# Oscilloscope.net
KiCad netlist of a schematic drawn in Altium Designer
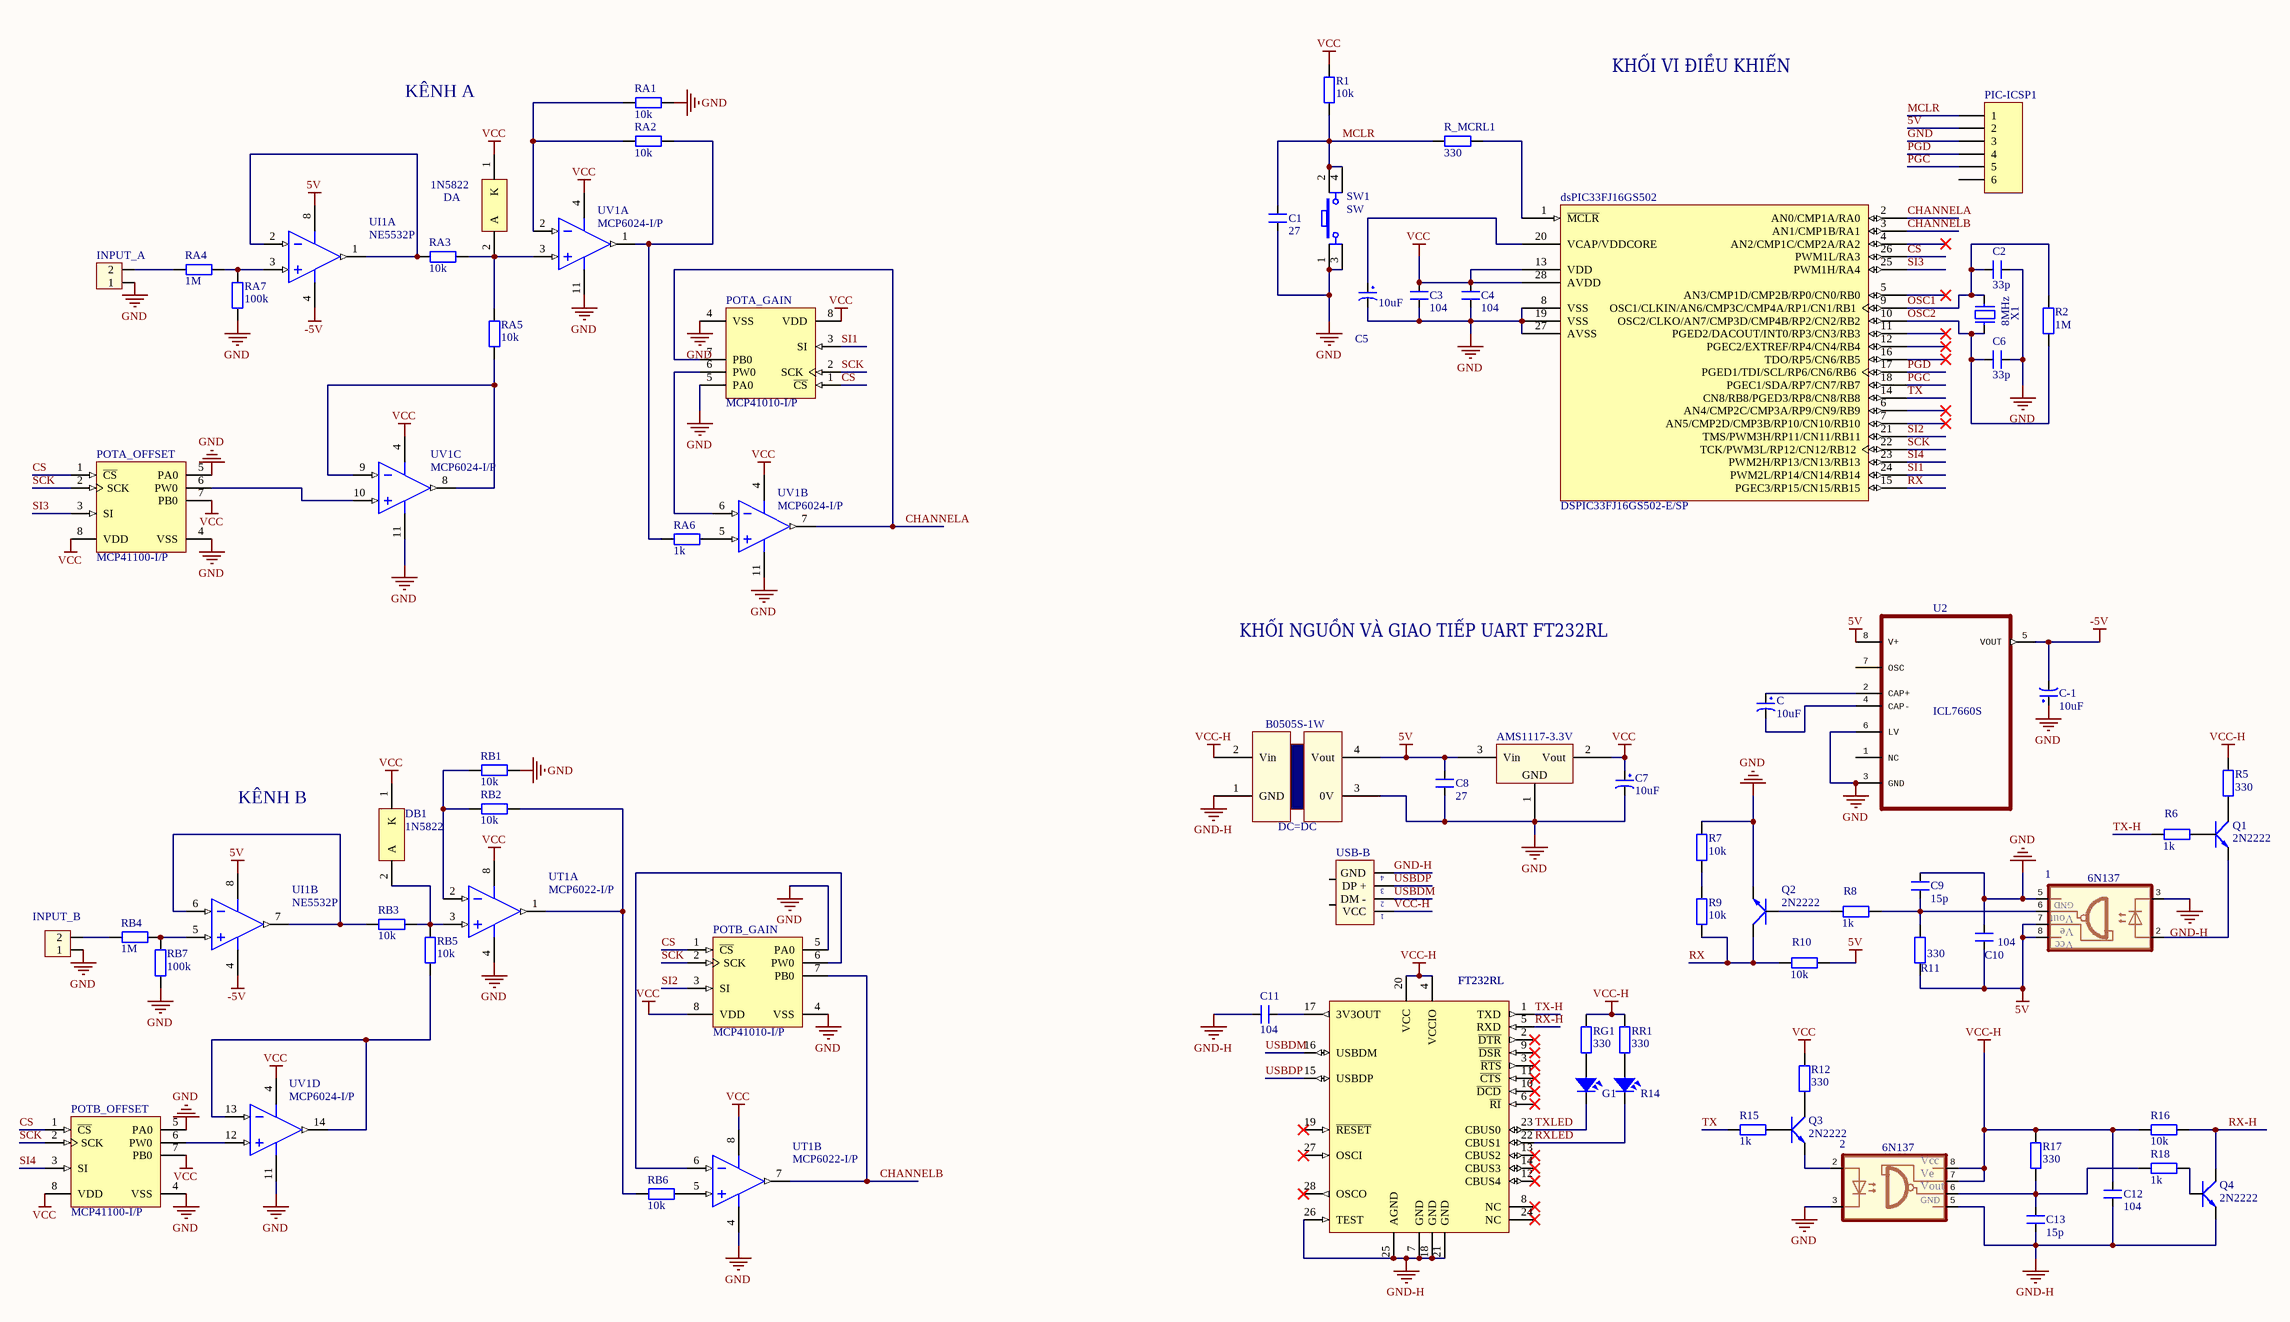
[diagram p0: Oscilloscope.SchDoc]

(export (version "E")
  (design (tool "Eeschema 10.0.6"))
  (components
    (comp (ref "1") (value "6N137") (footprint "DIP8/W0.3") (libsource (lib "6N137") (part "6N137")))
    (comp (ref "2") (value "6N137") (footprint "DIP8/W0.3") (libsource (lib "") (part "6N137_1")))
    (comp (ref "AMS1117-3.3V")
      (value "AMS1117-3V3")
      (footprint "TO-252")
      (libsource (lib "AMS1117-3V3") (part "AMS1117-3V3"))
    )
    (comp (ref "B0505S-1W")
      (value "DC=DC")
      (footprint "B050S-1W")
      (description "NGUON CACH LY")
      (libsource (lib "B0505S-1W") (part "B050S-1W"))
    )
    (comp (ref "C")
      (value "10uF")
      (footprint "CP1/2")
      (description "Cap P  0,1uF < 22uF , 16 - 50V")
      (libsource (lib "syhaunguyen") (part "CP1"))
    )
    (comp (ref "C-1")
      (value "10uF")
      (footprint "CP1/2")
      (description "Cap P  0,1uF < 22uF , 16 - 50V")
      (libsource (lib "syhaunguyen") (part "CP1"))
    )
    (comp (ref "C1")
      (value "27")
      (footprint "CN1.5")
      (description "Cap np 682pF => 104pF")
      (libsource (lib "syhaunguyen") (part "CN1.5"))
    )
    (comp (ref "C2")
      (value "33p")
      (footprint "CN1.5")
      (description "Cap np 682pF => 104pF")
      (libsource (lib "syhaunguyen") (part "CN1.5"))
    )
    (comp (ref "C3")
      (value "104")
      (footprint "CN1.5")
      (description "Cap np 682pF => 104pF")
      (libsource (lib "syhaunguyen") (part "CN1.5"))
    )
    (comp (ref "C4")
      (value "104")
      (footprint "CN1.5")
      (description "Cap np 682pF => 104pF")
      (libsource (lib "syhaunguyen") (part "CN1.5"))
    )
    (comp (ref "C5")
      (value "10uF")
      (footprint "CP1/2")
      (description "Cap P  0,1uF < 22uF , 16 - 50V")
      (libsource (lib "syhaunguyen") (part "CP1"))
    )
    (comp (ref "C6")
      (value "33p")
      (footprint "CN1.5")
      (description "Cap np 682pF => 104pF")
      (libsource (lib "syhaunguyen") (part "CN1.5"))
    )
    (comp (ref "C7")
      (value "10uF")
      (footprint "CP1/2")
      (description "Cap P  0,1uF < 22uF , 16 - 50V")
      (libsource (lib "syhaunguyen") (part "CP1"))
    )
    (comp (ref "C8")
      (value "27")
      (footprint "CN1.5")
      (description "Cap np 682pF => 104pF")
      (libsource (lib "syhaunguyen") (part "CN1.5"))
    )
    (comp (ref "C9")
      (value "15p")
      (footprint "CN1.5")
      (description "Cap np 682pF => 104pF")
      (libsource (lib "electronicvn-library1") (part "CN1.5"))
    )
    (comp (ref "C10")
      (value "104")
      (footprint "CN1.5")
      (description "Cap np 682pF => 104pF")
      (libsource (lib "electronicvn-library1") (part "CN1.5"))
    )
    (comp (ref "C11")
      (value "104")
      (footprint "CN1.5")
      (description "Cap np 682pF => 104pF")
      (libsource (lib "syhaunguyen") (part "CN1.5"))
    )
    (comp (ref "C12")
      (value "104")
      (footprint "CN1.5")
      (description "Cap np 682pF => 104pF")
      (libsource (lib "electronicvn-library1") (part "CN1.5"))
    )
    (comp (ref "C13")
      (value "15p")
      (footprint "CN1.5")
      (description "Cap np 682pF => 104pF")
      (libsource (lib "electronicvn-library1") (part "CN1.5"))
    )
    (comp (ref "DA")
      (value "1N5822")
      (footprint "ONSC-AXIAL_LEAD-2-267-05_V")
      (description "Rectifier, 2-Pin Axial_Lead, Bulk Bag")
      (fields (field (name "MANUFACTURER") "On Semiconductor"))
      (libsource (lib "ON Semi Schottky Diodes & Schottky Rectifiers") (part "1N5822"))
    )
    (comp (ref "DB1")
      (value "1N5822")
      (footprint "ONSC-AXIAL_LEAD-2-267-05_V")
      (description "Rectifier, 2-Pin Axial_Lead, Bulk Bag")
      (fields (field (name "MANUFACTURER") "On Semiconductor"))
      (libsource (lib "ON Semi Schottky Diodes & Schottky Rectifiers") (part "1N5822"))
    )
    (comp (ref "dsPIC33FJ16GS502")
      (value "DSPIC33FJ16GS502-E/SP")
      (footprint "Dallas Communication PCM Circuit:DIP28W")
      (fields (field (name "PUBLISHER") "Altium Limited"))
      (libsource (lib "Microchip DSC 16-Bit dsPIC33F") (part "DSPIC33FJ16GS502-E/SP"))
    )
    (comp (ref "FT232RL")
      (value "FT232RL")
      (footprint "DIP28W")
      (description "USB UART Asynchronous Serial Data Transfer Chip, 28-pin SSOP, Tube")
      (fields (field (name "MANUFACTURER") "FTDI") (field (name "PARTNUMBER") "FT232RL-Tube"))
      (libsource (lib "FTDI FT Series") (part "FT232RL-Tube"))
    )
    (comp (ref "G1")
      (value "LED")
      (footprint "LED-5-Green")
      (description "LED Single colour Green and Red")
      (libsource (lib "electronicvn-library1") (part "LED"))
    )
    (comp (ref "INPUT_A")
      (value "Header 2")
      (footprint "HED2")
      (description "Header 2 (Green)")
      (libsource (lib "syhaunguyen") (part "Hed2"))
    )
    (comp (ref "INPUT_B")
      (value "Header 2")
      (footprint "HED2")
      (description "Header 2 (Green)")
      (libsource (lib "syhaunguyen") (part "Hed2"))
    )
    (comp (ref "PIC-ICSP1")
      (value "PIC-ICSP-UART")
      (footprint "HDR1X6 - L")
      (description "Header, 6-Pin")
      (fields (field (name "PUBLISHER") "Altium Limited"))
      (libsource (lib "NBBLib 14-03-2012") (part "Header 6L"))
    )
    (comp (ref "POTA_GAIN")
      (value "MCP41010-I/P")
      (footprint "PDIP300-P8")
      (description "Single/Dual Digital Potentiometer with SPI Interface, 8-Pin PDIP, Industrial Temperature")
      (fields (field (name "PUBLISHER") "Altium Limited"))
      (libsource (lib "") (part "MCP41100-I/P_1"))
    )
    (comp (ref "POTA_OFFSET")
      (value "MCP41100-I/P")
      (footprint "PDIP300-P8")
      (description "Single/Dual Digital Potentiometer with SPI Interface, 8-Pin PDIP, Industrial Temperature")
      (fields (field (name "PUBLISHER") "Altium Limited"))
      (libsource (lib "Microchip Mixed Signal") (part "MCP41100-I/P"))
    )
    (comp (ref "POTB_GAIN")
      (value "MCP41010-I/P")
      (footprint "PDIP300-P8")
      (description "Single/Dual Digital Potentiometer with SPI Interface, 8-Pin PDIP, Industrial Temperature")
      (fields (field (name "PUBLISHER") "Altium Limited"))
      (libsource (lib "Microchip Mixed Signal") (part "MCP41100-I/P"))
    )
    (comp (ref "POTB_OFFSET")
      (value "MCP41100-I/P")
      (footprint "PDIP300-P8")
      (description "Single/Dual Digital Potentiometer with SPI Interface, 8-Pin PDIP, Industrial Temperature")
      (fields (field (name "PUBLISHER") "Altium Limited"))
      (libsource (lib "Microchip Mixed Signal") (part "MCP41100-I/P"))
    )
    (comp (ref "Q1")
      (value "2N2222")
      (footprint "QTO-92")
      (description "P 600mW, EBC")
      (libsource (lib "syhaunguyen") (part "NPN_EBC"))
    )
    (comp (ref "Q2")
      (value "2N2222")
      (footprint "QTO-92")
      (description "P 600mW, EBC")
      (libsource (lib "syhaunguyen") (part "NPN_EBC"))
    )
    (comp (ref "Q3")
      (value "2N2222")
      (footprint "QTO-92")
      (description "P 600mW, EBC")
      (libsource (lib "syhaunguyen") (part "NPN_EBC"))
    )
    (comp (ref "Q4")
      (value "2N2222")
      (footprint "QTO-92")
      (description "P 600mW, EBC")
      (libsource (lib "syhaunguyen") (part "NPN_EBC"))
    )
    (comp (ref "R1")
      (value "10k")
      (footprint "R1/2W")
      (description "Resistor 1/4W")
      (libsource (lib "syhaunguyen") (part "R1/4W"))
    )
    (comp (ref "R2")
      (value "1M")
      (footprint "R1/2W")
      (description "Resistor 1/4W")
      (libsource (lib "syhaunguyen") (part "R1/4W"))
    )
    (comp (ref "R5")
      (value "330")
      (footprint "R1/4W")
      (description "Resistor 1/4W")
      (libsource (lib "syhaunguyen") (part "R1/4W"))
    )
    (comp (ref "R6")
      (value "1k")
      (footprint "R1/4W")
      (description "Resistor 1/4W")
      (libsource (lib "syhaunguyen") (part "R1/4W"))
    )
    (comp (ref "R7")
      (value "10k")
      (footprint "R1/4W")
      (description "Resistor 1/4W")
      (libsource (lib "syhaunguyen") (part "R1/4W"))
    )
    (comp (ref "R8")
      (value "1k")
      (footprint "R1/4W")
      (description "Resistor 1/4W")
      (libsource (lib "syhaunguyen") (part "R1/4W"))
    )
    (comp (ref "R9")
      (value "10k")
      (footprint "R1/4W")
      (description "Resistor 1/4W")
      (libsource (lib "syhaunguyen") (part "R1/4W"))
    )
    (comp (ref "R10")
      (value "10k")
      (footprint "R1/4W")
      (description "Resistor 1/4W")
      (libsource (lib "syhaunguyen") (part "R1/4W"))
    )
    (comp (ref "R11")
      (value "330")
      (footprint "R1/4W")
      (description "Resistor 1/4W")
      (libsource (lib "syhaunguyen") (part "R1/4W"))
    )
    (comp (ref "R12")
      (value "330")
      (footprint "R1/4W")
      (description "Resistor 1/4W")
      (libsource (lib "syhaunguyen") (part "R1/4W"))
    )
    (comp (ref "R14")
      (value "LED")
      (footprint "LED-5-RED")
      (description "LED Single colour Green and Red")
      (libsource (lib "electronicvn-library1") (part "LED"))
    )
    (comp (ref "R15")
      (value "1k")
      (footprint "R1/4W")
      (description "Resistor 1/4W")
      (libsource (lib "syhaunguyen") (part "R1/4W"))
    )
    (comp (ref "R16")
      (value "10k")
      (footprint "R1/4W")
      (description "Resistor 1/4W")
      (libsource (lib "syhaunguyen") (part "R1/4W"))
    )
    (comp (ref "R17")
      (value "330")
      (footprint "R1/4W")
      (description "Resistor 1/4W")
      (libsource (lib "syhaunguyen") (part "R1/4W"))
    )
    (comp (ref "R18")
      (value "1k")
      (footprint "R1/4W")
      (description "Resistor 1/4W")
      (libsource (lib "syhaunguyen") (part "R1/4W"))
    )
    (comp (ref "RA1")
      (value "10k")
      (footprint "R1/2W")
      (description "Resistor 1/4W")
      (libsource (lib "syhaunguyen") (part "R1/4W"))
    )
    (comp (ref "RA2")
      (value "10k")
      (footprint "R1/2W")
      (description "Resistor 1/4W")
      (libsource (lib "syhaunguyen") (part "R1/4W"))
    )
    (comp (ref "RA3")
      (value "10k")
      (footprint "R1/2W")
      (description "Resistor 1/4W")
      (libsource (lib "syhaunguyen") (part "R1/4W"))
    )
    (comp (ref "RA4")
      (value "1M")
      (footprint "R1/2W")
      (description "Resistor 1/4W")
      (libsource (lib "syhaunguyen") (part "R1/4W"))
    )
    (comp (ref "RA5")
      (value "10k")
      (footprint "R1/2W")
      (description "Resistor 1/4W")
      (libsource (lib "syhaunguyen") (part "R1/4W"))
    )
    (comp (ref "RA6")
      (value "1k")
      (footprint "R1/2W")
      (description "Resistor 1/4W")
      (libsource (lib "syhaunguyen") (part "R1/4W"))
    )
    (comp (ref "RA7")
      (value "100k")
      (footprint "R1/2W")
      (description "Resistor 1/4W")
      (libsource (lib "syhaunguyen") (part "R1/4W"))
    )
    (comp (ref "RB1")
      (value "10k")
      (footprint "R1/2W")
      (description "Resistor 1/4W")
      (libsource (lib "syhaunguyen") (part "R1/4W"))
    )
    (comp (ref "RB2")
      (value "10k")
      (footprint "R1/2W")
      (description "Resistor 1/4W")
      (libsource (lib "syhaunguyen") (part "R1/4W"))
    )
    (comp (ref "RB3")
      (value "10k")
      (footprint "R1/2W")
      (description "Resistor 1/4W")
      (libsource (lib "syhaunguyen") (part "R1/4W"))
    )
    (comp (ref "RB4")
      (value "1M")
      (footprint "R1/2W")
      (description "Resistor 1/4W")
      (libsource (lib "syhaunguyen") (part "R1/4W"))
    )
    (comp (ref "RB5")
      (value "10k")
      (footprint "R1/2W")
      (description "Resistor 1/4W")
      (libsource (lib "syhaunguyen") (part "R1/4W"))
    )
    (comp (ref "RB6")
      (value "10k")
      (footprint "R1/2W")
      (description "Resistor 1/4W")
      (libsource (lib "syhaunguyen") (part "R1/4W"))
    )
    (comp (ref "RB7")
      (value "100k")
      (footprint "R1/2W")
      (description "Resistor 1/4W")
      (libsource (lib "syhaunguyen") (part "R1/4W"))
    )
    (comp (ref "RG1")
      (value "330")
      (footprint "R1/4W")
      (description "Resistor 1/4W")
      (libsource (lib "syhaunguyen") (part "R1/4W"))
    )
    (comp (ref "RR1")
      (value "330")
      (footprint "R1/4W")
      (description "Resistor 1/4W")
      (libsource (lib "syhaunguyen") (part "R1/4W"))
    )
    (comp (ref "R_MCRL1")
      (value "330")
      (footprint "R1/2W")
      (description "Resistor 1/4W")
      (libsource (lib "syhaunguyen") (part "R1/4W"))
    )
    (comp (ref "SW1")
      (value "SW")
      (footprint "SW4")
      (description "Switch button 4 pin")
      (libsource (lib "syhaunguyen") (part "SW4"))
    )
    (comp (ref "U2")
      (value "ICL7660S")
      (footprint "DIP-8")
      (libsource (lib "ICL7660CPAZ") (part "ICL7660CPAZ"))
    )
    (comp (ref "UI1")
      (value "NE5532P")
      (footprint "TI-P8")
      (fields (field (name "MANUFACTURER") "Texas Instruments"))
      (libsource (lib "TI Amplifiers and Linear Operational Amplifier General Purpose") (part "NE5532P"))
    )
    (comp (ref "USB-B")
      (value "USB")
      (footprint "USB-B-MALE")
      (description "USB connector")
      (libsource (lib "PART") (part "USB"))
    )
    (comp (ref "UT1")
      (value "MCP6022-I/P")
      (footprint "PDIP300-P8")
      (description "Rail-to-Rail Input/Output, 10 MHz Operational Amplifier, 8-Pin PDIP, Industrial Temperature")
      (fields (field (name "MANUFACTURER") "Microchip"))
      (libsource (lib "Microchip Linear") (part "MCP6022-I/P"))
    )
    (comp (ref "UV1")
      (value "MCP6024-I/P")
      (footprint "PDIP300-P14")
      (description "Rail-to-Rail Input/Output, 10 MHz Operational Amplifier, 14-Pin PDIP, Industrial Temperature")
      (fields (field (name "MANUFACTURER") "Microchip"))
      (libsource (lib "Microchip Linear") (part "MCP6024-I/P"))
    )
    (comp (ref "X1")
      (value "8MHz")
      (footprint "XT2")
      (description "Crystal For all Crystal 2pin.")
      (libsource (lib "PART") (part "XT2"))
    )
  )
  (nets
    (net (code "1") (name "-5V") (class "Default")
      (node (ref "C-1") (pin "2") (pinfunction "2_2") (pintype "passive"))
      (node (ref "U2") (pin "5") (pinfunction "VOUT_5") (pintype "output"))
      (node (ref "UI1") (pin "4") (pinfunction "VCC-_4") (pintype "power_in"))
    )
    (net (code "2") (name "/CHANNELA") (class "Default")
      (node (ref "POTA_GAIN") (pin "7") (pinfunction "PB0_7") (pintype "passive"))
      (node (ref "UV1") (pin "7") (pinfunction "VOUTB_7") (pintype "output"))
      (node (ref "dsPIC33FJ16GS502") (pin "2") (pinfunction "AN0/CMP1A/RA0_2") (pintype "bidirectional"))
    )
    (net (code "3") (name "/CHANNELB") (class "Default")
      (node (ref "POTB_GAIN") (pin "7") (pinfunction "PB0_7") (pintype "passive"))
      (node (ref "UT1") (pin "7") (pinfunction "VOUTB_7") (pintype "output"))
      (node (ref "dsPIC33FJ16GS502") (pin "3") (pinfunction "AN1/CMP1B/RA1_3") (pintype "bidirectional"))
    )
    (net (code "4") (name "/CS") (class "Default")
      (node (ref "POTA_GAIN") (pin "1") (pinfunction "~{CS}_1") (pintype "input"))
      (node (ref "POTA_OFFSET") (pin "1") (pinfunction "~{CS}_1") (pintype "input"))
      (node (ref "POTB_GAIN") (pin "1") (pinfunction "~{CS}_1") (pintype "input"))
      (node (ref "POTB_OFFSET") (pin "1") (pinfunction "~{CS}_1") (pintype "input"))
      (node (ref "dsPIC33FJ16GS502") (pin "26") (pinfunction "PWM1L/RA3_26") (pintype "bidirectional"))
    )
    (net (code "5") (name "/MCLR") (class "Default")
      (node (ref "C1") (pin "2") (pinfunction "2_2") (pintype "passive"))
      (node (ref "PIC-ICSP1") (pin "1") (pinfunction "1_1") (pintype "passive"))
      (node (ref "R1") (pin "1") (pinfunction "1_1") (pintype "passive"))
      (node (ref "R_MCRL1") (pin "2") (pinfunction "2_2") (pintype "passive"))
      (node (ref "SW1") (pin "2") (pintype "passive"))
      (node (ref "SW1") (pin "4") (pintype "passive"))
    )
    (net (code "6") (name "/OSC1") (class "Default")
      (node (ref "C2") (pin "1") (pinfunction "1_1") (pintype "passive"))
      (node (ref "R2") (pin "2") (pinfunction "2_2") (pintype "passive"))
      (node (ref "X1") (pin "2") (pinfunction "2_2") (pintype "passive"))
      (node (ref "dsPIC33FJ16GS502") (pin "9") (pinfunction "OSC1/CLKIN/AN6/CMP3C/CMP4A/RP1/CN1/RB1_9") (pintype "bidirectional"))
    )
    (net (code "7") (name "/OSC2") (class "Default")
      (node (ref "C6") (pin "1") (pinfunction "1_1") (pintype "passive"))
      (node (ref "R2") (pin "1") (pinfunction "1_1") (pintype "passive"))
      (node (ref "X1") (pin "1") (pinfunction "1_1") (pintype "passive"))
      (node (ref "dsPIC33FJ16GS502") (pin "10") (pinfunction "OSC2/CLKO/AN7/CMP3D/CMP4B/RP2/CN2/RB2_10") (pintype "bidirectional"))
    )
    (net (code "8") (name "/PGC") (class "Default")
      (node (ref "PIC-ICSP1") (pin "5") (pinfunction "5_5") (pintype "passive"))
      (node (ref "dsPIC33FJ16GS502") (pin "18") (pinfunction "PGEC1/SDA/RP7/CN7/RB7_18") (pintype "bidirectional"))
    )
    (net (code "9") (name "/PGD") (class "Default")
      (node (ref "PIC-ICSP1") (pin "4") (pinfunction "4_4") (pintype "passive"))
      (node (ref "dsPIC33FJ16GS502") (pin "17") (pinfunction "PGED1/TDI/SCL/RP6/CN6/RB6_17") (pintype "bidirectional"))
    )
    (net (code "10") (name "/RX") (class "Default")
      (node (ref "Q2") (pin "3") (pinfunction "C_3") (pintype "passive"))
      (node (ref "R10") (pin "1") (pinfunction "1_1") (pintype "passive"))
      (node (ref "R9") (pin "1") (pinfunction "1_1") (pintype "passive"))
      (node (ref "dsPIC33FJ16GS502") (pin "15") (pinfunction "PGEC3/RP15/CN15/RB15_15") (pintype "bidirectional"))
    )
    (net (code "11") (name "/RX-H") (class "Default")
      (node (ref "FT232RL") (pin "5") (pinfunction "RXD_5") (pintype "input"))
      (node (ref "Q4") (pin "3") (pinfunction "C_3") (pintype "passive"))
      (node (ref "R16") (pin "2") (pinfunction "2_2") (pintype "passive"))
    )
    (net (code "12") (name "/RXLED") (class "Default")
      (node (ref "FT232RL") (pin "22") (pinfunction "CBUS1_22") (pintype "bidirectional"))
      (node (ref "R14") (pin "2") (pinfunction "2_2") (pintype "passive"))
    )
    (net (code "13") (name "/SCK") (class "Default")
      (node (ref "POTA_GAIN") (pin "2") (pinfunction "SCK_2") (pintype "input"))
      (node (ref "POTA_OFFSET") (pin "2") (pinfunction "SCK_2") (pintype "input"))
      (node (ref "POTB_GAIN") (pin "2") (pinfunction "SCK_2") (pintype "input"))
      (node (ref "POTB_OFFSET") (pin "2") (pinfunction "SCK_2") (pintype "input"))
      (node (ref "dsPIC33FJ16GS502") (pin "22") (pinfunction "TCK/PWM3L/RP12/CN12/RB12_22") (pintype "bidirectional"))
    )
    (net (code "14") (name "/SI1") (class "Default")
      (node (ref "POTA_GAIN") (pin "3") (pinfunction "SI_3") (pintype "input"))
      (node (ref "dsPIC33FJ16GS502") (pin "24") (pinfunction "PWM2L/RP14/CN14/RB14_24") (pintype "bidirectional"))
    )
    (net (code "15") (name "/SI2") (class "Default")
      (node (ref "POTB_GAIN") (pin "3") (pinfunction "SI_3") (pintype "input"))
      (node (ref "dsPIC33FJ16GS502") (pin "21") (pinfunction "TMS/PWM3H/RP11/CN11/RB11_21") (pintype "bidirectional"))
    )
    (net (code "16") (name "/SI3") (class "Default")
      (node (ref "POTA_OFFSET") (pin "3") (pinfunction "SI_3") (pintype "input"))
      (node (ref "dsPIC33FJ16GS502") (pin "25") (pinfunction "PWM1H/RA4_25") (pintype "bidirectional"))
    )
    (net (code "17") (name "/SI4") (class "Default")
      (node (ref "POTB_OFFSET") (pin "3") (pinfunction "SI_3") (pintype "input"))
      (node (ref "dsPIC33FJ16GS502") (pin "23") (pinfunction "PWM2H/RP13/CN13/RB13_23") (pintype "bidirectional"))
    )
    (net (code "18") (name "/TX") (class "Default")
      (node (ref "R15") (pin "1") (pinfunction "1_1") (pintype "passive"))
      (node (ref "dsPIC33FJ16GS502") (pin "14") (pinfunction "CN8/RB8/PGED3/RP8/CN8/RB8_14") (pintype "bidirectional"))
    )
    (net (code "19") (name "/TX-H") (class "Default")
      (node (ref "FT232RL") (pin "1") (pinfunction "TXD_1") (pintype "output"))
      (node (ref "R6") (pin "1") (pinfunction "1_1") (pintype "passive"))
    )
    (net (code "20") (name "/TXLED") (class "Default")
      (node (ref "FT232RL") (pin "23") (pinfunction "CBUS0_23") (pintype "bidirectional"))
      (node (ref "G1") (pin "2") (pinfunction "2_2") (pintype "passive"))
    )
    (net (code "21") (name "/USBDM") (class "Default")
      (node (ref "FT232RL") (pin "16") (pinfunction "USBDM_16") (pintype "bidirectional"))
      (node (ref "USB-B") (pin "2") (pinfunction "DM_-_2") (pintype "passive"))
    )
    (net (code "22") (name "/USBDP") (class "Default")
      (node (ref "FT232RL") (pin "15") (pinfunction "USBDP_15") (pintype "bidirectional"))
      (node (ref "USB-B") (pin "3") (pinfunction "DP_+_3") (pintype "passive"))
    )
    (net (code "23") (name "5V") (class "Default")
      (node (ref "1") (pin "7") (pinfunction "VE_7") (pintype "passive"))
      (node (ref "1") (pin "8") (pinfunction "VCC_8") (pintype "passive"))
      (node (ref "AMS1117-3.3V") (pin "3") (pinfunction "Vin_3") (pintype "power_in"))
      (node (ref "B0505S-1W") (pin "4") (pinfunction "Vout_4") (pintype "passive"))
      (node (ref "C10") (pin "1") (pinfunction "1_1") (pintype "passive"))
      (node (ref "C8") (pin "2") (pinfunction "2_2") (pintype "passive"))
      (node (ref "PIC-ICSP1") (pin "2") (pinfunction "2_2") (pintype "passive"))
      (node (ref "R10") (pin "2") (pinfunction "2_2") (pintype "passive"))
      (node (ref "R11") (pin "1") (pinfunction "1_1") (pintype "passive"))
      (node (ref "U2") (pin "8") (pinfunction "V+_8") (pintype "power_in"))
      (node (ref "UI1") (pin "8") (pinfunction "VCC+_8") (pintype "power_in"))
    )
    (net (code "24") (name "GND") (class "Default")
      (node (ref "1") (pin "5") (pinfunction "GND_5") (pintype "passive"))
      (node (ref "2") (pin "3") (pinfunction "C_3") (pintype "passive"))
      (node (ref "AMS1117-3.3V") (pin "1") (pinfunction "GND_1") (pintype "power_in"))
      (node (ref "B0505S-1W") (pin "3") (pinfunction "0V_3") (pintype "passive"))
      (node (ref "C-1") (pin "1") (pinfunction "1_1") (pintype "passive"))
      (node (ref "C1") (pin "1") (pinfunction "1_1") (pintype "passive"))
      (node (ref "C10") (pin "2") (pinfunction "2_2") (pintype "passive"))
      (node (ref "C2") (pin "2") (pinfunction "2_2") (pintype "passive"))
      (node (ref "C3") (pin "1") (pinfunction "1_1") (pintype "passive"))
      (node (ref "C4") (pin "1") (pinfunction "1_1") (pintype "passive"))
      (node (ref "C5") (pin "2") (pinfunction "2_2") (pintype "passive"))
      (node (ref "C6") (pin "2") (pinfunction "2_2") (pintype "passive"))
      (node (ref "C7") (pin "2") (pinfunction "2_2") (pintype "passive"))
      (node (ref "C8") (pin "1") (pinfunction "1_1") (pintype "passive"))
      (node (ref "C9") (pin "2") (pinfunction "2_2") (pintype "passive"))
      (node (ref "INPUT_A") (pin "1") (pinfunction "1_1") (pintype "passive"))
      (node (ref "INPUT_B") (pin "1") (pinfunction "1_1") (pintype "passive"))
      (node (ref "PIC-ICSP1") (pin "3") (pinfunction "3_3") (pintype "passive"))
      (node (ref "POTA_GAIN") (pin "4") (pinfunction "VSS_4") (pintype "power_in"))
      (node (ref "POTA_GAIN") (pin "5") (pinfunction "PA0_5") (pintype "passive"))
      (node (ref "POTA_OFFSET") (pin "4") (pinfunction "VSS_4") (pintype "power_in"))
      (node (ref "POTA_OFFSET") (pin "5") (pinfunction "PA0_5") (pintype "passive"))
      (node (ref "POTB_GAIN") (pin "4") (pinfunction "VSS_4") (pintype "power_in"))
      (node (ref "POTB_GAIN") (pin "5") (pinfunction "PA0_5") (pintype "passive"))
      (node (ref "POTB_OFFSET") (pin "4") (pinfunction "VSS_4") (pintype "power_in"))
      (node (ref "POTB_OFFSET") (pin "5") (pinfunction "PA0_5") (pintype "passive"))
      (node (ref "Q2") (pin "1") (pinfunction "E_1") (pintype "passive"))
      (node (ref "R7") (pin "2") (pinfunction "2_2") (pintype "passive"))
      (node (ref "RA1") (pin "1") (pinfunction "1_1") (pintype "passive"))
      (node (ref "RA7") (pin "1") (pinfunction "1_1") (pintype "passive"))
      (node (ref "RB1") (pin "1") (pinfunction "1_1") (pintype "passive"))
      (node (ref "RB7") (pin "1") (pinfunction "1_1") (pintype "passive"))
      (node (ref "SW1") (pin "1") (pintype "passive"))
      (node (ref "SW1") (pin "3") (pintype "passive"))
      (node (ref "U2") (pin "3") (pinfunction "GND_3") (pintype "passive"))
      (node (ref "U2") (pin "6") (pinfunction "LV_6") (pintype "passive"))
      (node (ref "UT1") (pin "4") (pinfunction "VSS_4") (pintype "power_in"))
      (node (ref "UV1") (pin "11") (pinfunction "VSS_11") (pintype "power_in"))
      (node (ref "dsPIC33FJ16GS502") (pin "19") (pinfunction "VSS_19") (pintype "power_in"))
      (node (ref "dsPIC33FJ16GS502") (pin "27") (pinfunction "AVSS_27") (pintype "power_in"))
      (node (ref "dsPIC33FJ16GS502") (pin "8") (pinfunction "VSS_8") (pintype "power_in"))
    )
    (net (code "25") (name "GND-H") (class "Default")
      (node (ref "1") (pin "3") (pinfunction "C_3") (pintype "passive"))
      (node (ref "2") (pin "5") (pinfunction "GND_5") (pintype "passive"))
      (node (ref "B0505S-1W") (pin "1") (pinfunction "GND_1") (pintype "passive"))
      (node (ref "C11") (pin "1") (pinfunction "1_1") (pintype "passive"))
      (node (ref "C12") (pin "1") (pinfunction "1_1") (pintype "passive"))
      (node (ref "C13") (pin "1") (pinfunction "1_1") (pintype "passive"))
      (node (ref "FT232RL") (pin "18") (pinfunction "GND_18") (pintype "power_in"))
      (node (ref "FT232RL") (pin "21") (pinfunction "GND_21") (pintype "power_in"))
      (node (ref "FT232RL") (pin "25") (pinfunction "AGND_25") (pintype "power_in"))
      (node (ref "FT232RL") (pin "26") (pinfunction "TEST_26") (pintype "input"))
      (node (ref "FT232RL") (pin "7") (pinfunction "GND_7") (pintype "power_in"))
      (node (ref "Q4") (pin "1") (pinfunction "E_1") (pintype "passive"))
      (node (ref "USB-B") (pin "4") (pinfunction "GND_4") (pintype "passive"))
    )
    (net (code "26") (name "Net-(1-A)") (class "Default")
      (node (ref "1") (pin "2") (pinfunction "A_2") (pintype "passive"))
      (node (ref "Q1") (pin "1") (pinfunction "E_1") (pintype "passive"))
    )
    (net (code "27") (name "Net-(1-VO)") (class "Default")
      (node (ref "1") (pin "6") (pinfunction "VO_6") (pintype "passive"))
      (node (ref "C9") (pin "1") (pinfunction "1_1") (pintype "passive"))
      (node (ref "R11") (pin "2") (pinfunction "2_2") (pintype "passive"))
      (node (ref "R8") (pin "2") (pinfunction "2_2") (pintype "passive"))
    )
    (net (code "28") (name "Net-(2-A)") (class "Default")
      (node (ref "2") (pin "2") (pinfunction "A_2") (pintype "passive"))
      (node (ref "Q3") (pin "1") (pinfunction "E_1") (pintype "passive"))
    )
    (net (code "29") (name "Net-(2-VO)") (class "Default")
      (node (ref "2") (pin "6") (pinfunction "VO_6") (pintype "passive"))
      (node (ref "C13") (pin "2") (pinfunction "2_2") (pintype "passive"))
      (node (ref "R17") (pin "1") (pinfunction "1_1") (pintype "passive"))
      (node (ref "R18") (pin "1") (pinfunction "1_1") (pintype "passive"))
    )
    (net (code "30") (name "Net-(DA-A)") (class "Default")
      (node (ref "DA") (pin "2") (pinfunction "A_2") (pintype "passive"))
      (node (ref "RA3") (pin "1") (pinfunction "1_1") (pintype "passive"))
      (node (ref "RA5") (pin "1") (pinfunction "1_1") (pintype "passive"))
      (node (ref "UV1") (pin "3") (pinfunction "VINA+_3") (pintype "input"))
    )
    (net (code "31") (name "Net-(DB1-A)") (class "Default")
      (node (ref "DB1") (pin "2") (pinfunction "A_2") (pintype "passive"))
      (node (ref "RB3") (pin "1") (pinfunction "1_1") (pintype "passive"))
      (node (ref "RB5") (pin "2") (pinfunction "2_2") (pintype "passive"))
      (node (ref "UT1") (pin "3") (pinfunction "VINA+_3") (pintype "input"))
    )
    (net (code "32") (name "Net-(FT232RL-3V3OUT)") (class "Default")
      (node (ref "C11") (pin "2") (pinfunction "2_2") (pintype "passive"))
      (node (ref "FT232RL") (pin "17") (pinfunction "3V3OUT_17") (pintype "output"))
    )
    (net (code "33") (name "Net-(G1-Pad1)") (class "Default")
      (node (ref "G1") (pin "1") (pinfunction "1_1") (pintype "passive"))
      (node (ref "RG1") (pin "1") (pinfunction "1_1") (pintype "passive"))
    )
    (net (code "34") (name "Net-(INPUT_A-Pad2)") (class "Default")
      (node (ref "INPUT_A") (pin "2") (pinfunction "2_2") (pintype "passive"))
      (node (ref "RA4") (pin "2") (pinfunction "2_2") (pintype "passive"))
    )
    (net (code "35") (name "Net-(INPUT_B-Pad2)") (class "Default")
      (node (ref "INPUT_B") (pin "2") (pinfunction "2_2") (pintype "passive"))
      (node (ref "RB4") (pin "2") (pinfunction "2_2") (pintype "passive"))
    )
    (net (code "36") (name "Net-(POTA_GAIN-PW0)") (class "Default")
      (node (ref "POTA_GAIN") (pin "6") (pinfunction "PW0_6") (pintype "passive"))
      (node (ref "UV1") (pin "6") (pinfunction "VINB-_6") (pintype "input"))
    )
    (net (code "37") (name "Net-(POTA_OFFSET-PW0)") (class "Default")
      (node (ref "POTA_OFFSET") (pin "6") (pinfunction "PW0_6") (pintype "passive"))
      (node (ref "UV1") (pin "10") (pinfunction "VINC+_10") (pintype "input"))
    )
    (net (code "38") (name "Net-(POTB_GAIN-PW0)") (class "Default")
      (node (ref "POTB_GAIN") (pin "6") (pinfunction "PW0_6") (pintype "passive"))
      (node (ref "UT1") (pin "6") (pinfunction "VINB-_6") (pintype "input"))
    )
    (net (code "39") (name "Net-(POTB_OFFSET-PW0)") (class "Default")
      (node (ref "POTB_OFFSET") (pin "6") (pinfunction "PW0_6") (pintype "passive"))
      (node (ref "UV1") (pin "12") (pinfunction "VIND+_12") (pintype "input"))
    )
    (net (code "40") (name "Net-(Q1-B)") (class "Default")
      (node (ref "Q1") (pin "2") (pinfunction "B_2") (pintype "passive"))
      (node (ref "R6") (pin "2") (pinfunction "2_2") (pintype "passive"))
    )
    (net (code "41") (name "Net-(Q1-C)") (class "Default")
      (node (ref "Q1") (pin "3") (pinfunction "C_3") (pintype "passive"))
      (node (ref "R5") (pin "1") (pinfunction "1_1") (pintype "passive"))
    )
    (net (code "42") (name "Net-(Q2-B)") (class "Default")
      (node (ref "Q2") (pin "2") (pinfunction "B_2") (pintype "passive"))
      (node (ref "R8") (pin "1") (pinfunction "1_1") (pintype "passive"))
    )
    (net (code "43") (name "Net-(Q3-B)") (class "Default")
      (node (ref "Q3") (pin "2") (pinfunction "B_2") (pintype "passive"))
      (node (ref "R15") (pin "2") (pinfunction "2_2") (pintype "passive"))
    )
    (net (code "44") (name "Net-(Q3-C)") (class "Default")
      (node (ref "Q3") (pin "3") (pinfunction "C_3") (pintype "passive"))
      (node (ref "R12") (pin "1") (pinfunction "1_1") (pintype "passive"))
    )
    (net (code "45") (name "Net-(Q4-B)") (class "Default")
      (node (ref "Q4") (pin "2") (pinfunction "B_2") (pintype "passive"))
      (node (ref "R18") (pin "2") (pinfunction "2_2") (pintype "passive"))
    )
    (net (code "46") (name "Net-(R7-Pad1)") (class "Default")
      (node (ref "R7") (pin "1") (pinfunction "1_1") (pintype "passive"))
      (node (ref "R9") (pin "2") (pinfunction "2_2") (pintype "passive"))
    )
    (net (code "47") (name "Net-(R14-Pad1)") (class "Default")
      (node (ref "R14") (pin "1") (pinfunction "1_1") (pintype "passive"))
      (node (ref "RR1") (pin "1") (pinfunction "1_1") (pintype "passive"))
    )
    (net (code "48") (name "Net-(U2-CAP+)") (class "Default")
      (node (ref "C") (pin "1") (pinfunction "1_1") (pintype "passive"))
      (node (ref "U2") (pin "2") (pinfunction "CAP+_2") (pintype "passive"))
    )
    (net (code "49") (name "Net-(U2-CAP-)") (class "Default")
      (node (ref "C") (pin "2") (pinfunction "2_2") (pintype "passive"))
      (node (ref "U2") (pin "4") (pinfunction "CAP-_4") (pintype "passive"))
    )
    (net (code "50") (name "Net-(UI1A-IN1+)") (class "Default")
      (node (ref "RA4") (pin "1") (pinfunction "1_1") (pintype "passive"))
      (node (ref "RA7") (pin "2") (pinfunction "2_2") (pintype "passive"))
      (node (ref "UI1") (pin "3") (pinfunction "IN1+_3") (pintype "input"))
    )
    (net (code "51") (name "Net-(UI1A-IN1-)") (class "Default")
      (node (ref "RA3") (pin "2") (pinfunction "2_2") (pintype "passive"))
      (node (ref "UI1") (pin "1") (pinfunction "OUT1_1") (pintype "output"))
      (node (ref "UI1") (pin "2") (pinfunction "IN1-_2") (pintype "input"))
    )
    (net (code "52") (name "Net-(UI1B-IN2+)") (class "Default")
      (node (ref "RB4") (pin "1") (pinfunction "1_1") (pintype "passive"))
      (node (ref "RB7") (pin "2") (pinfunction "2_2") (pintype "passive"))
      (node (ref "UI1") (pin "5") (pinfunction "IN2+_5") (pintype "input"))
    )
    (net (code "53") (name "Net-(UI1B-IN2-)") (class "Default")
      (node (ref "RB3") (pin "2") (pinfunction "2_2") (pintype "passive"))
      (node (ref "UI1") (pin "6") (pinfunction "IN2-_6") (pintype "input"))
      (node (ref "UI1") (pin "7") (pinfunction "OUT2_7") (pintype "output"))
    )
    (net (code "54") (name "Net-(UT1A-VINA-)") (class "Default")
      (node (ref "RB1") (pin "2") (pinfunction "2_2") (pintype "passive"))
      (node (ref "RB2") (pin "2") (pinfunction "2_2") (pintype "passive"))
      (node (ref "UT1") (pin "2") (pinfunction "VINA-_2") (pintype "input"))
    )
    (net (code "55") (name "Net-(UT1A-VOUTA)") (class "Default")
      (node (ref "RB2") (pin "1") (pinfunction "1_1") (pintype "passive"))
      (node (ref "RB6") (pin "2") (pinfunction "2_2") (pintype "passive"))
      (node (ref "UT1") (pin "1") (pinfunction "VOUTA_1") (pintype "output"))
    )
    (net (code "56") (name "Net-(UT1B-VINB+)") (class "Default")
      (node (ref "RB6") (pin "1") (pinfunction "1_1") (pintype "passive"))
      (node (ref "UT1") (pin "5") (pinfunction "VINB+_5") (pintype "input"))
    )
    (net (code "57") (name "Net-(UV1A-VINA-)") (class "Default")
      (node (ref "RA1") (pin "2") (pinfunction "2_2") (pintype "passive"))
      (node (ref "RA2") (pin "2") (pinfunction "2_2") (pintype "passive"))
      (node (ref "UV1") (pin "2") (pinfunction "VINA-_2") (pintype "input"))
    )
    (net (code "58") (name "Net-(UV1A-VOUTA)") (class "Default")
      (node (ref "RA2") (pin "1") (pinfunction "1_1") (pintype "passive"))
      (node (ref "RA6") (pin "2") (pinfunction "2_2") (pintype "passive"))
      (node (ref "UV1") (pin "1") (pinfunction "VOUTA_1") (pintype "output"))
    )
    (net (code "59") (name "Net-(UV1B-VINB+)") (class "Default")
      (node (ref "RA6") (pin "1") (pinfunction "1_1") (pintype "passive"))
      (node (ref "UV1") (pin "5") (pinfunction "VINB+_5") (pintype "input"))
    )
    (net (code "60") (name "Net-(UV1C-VINC-)") (class "Default")
      (node (ref "RA5") (pin "2") (pinfunction "2_2") (pintype "passive"))
      (node (ref "UV1") (pin "8") (pinfunction "VOUTC_8") (pintype "output"))
      (node (ref "UV1") (pin "9") (pinfunction "VINC-_9") (pintype "input"))
    )
    (net (code "61") (name "Net-(UV1D-VIND-)") (class "Default")
      (node (ref "RB5") (pin "1") (pinfunction "1_1") (pintype "passive"))
      (node (ref "UV1") (pin "13") (pinfunction "VIND-_13") (pintype "input"))
      (node (ref "UV1") (pin "14") (pinfunction "VOUTD_14") (pintype "output"))
    )
    (net (code "62") (name "Net-(dsPIC33FJ16GS502-VCAP{slash}VDDCORE)") (class "Default")
      (node (ref "C5") (pin "1") (pinfunction "1_1") (pintype "passive"))
      (node (ref "dsPIC33FJ16GS502") (pin "20") (pinfunction "VCAP/VDDCORE_20") (pintype "power_in"))
    )
    (net (code "63") (name "Net-(dsPIC33FJ16GS502-~{MCLR})") (class "Default")
      (node (ref "R_MCRL1") (pin "1") (pinfunction "1_1") (pintype "passive"))
      (node (ref "dsPIC33FJ16GS502") (pin "1") (pinfunction "~{MCLR}_1") (pintype "input"))
    )
    (net (code "64") (name "VCC") (class "Default")
      (node (ref "AMS1117-3.3V") (pin "2") (pinfunction "Vout_2") (pintype "power_in"))
      (node (ref "C3") (pin "2") (pinfunction "2_2") (pintype "passive"))
      (node (ref "C4") (pin "2") (pinfunction "2_2") (pintype "passive"))
      (node (ref "C7") (pin "1") (pinfunction "1_1") (pintype "passive"))
      (node (ref "DA") (pin "1") (pinfunction "K_1") (pintype "passive"))
      (node (ref "DB1") (pin "1") (pinfunction "K_1") (pintype "passive"))
      (node (ref "POTA_GAIN") (pin "8") (pinfunction "VDD_8") (pintype "power_in"))
      (node (ref "POTA_OFFSET") (pin "7") (pinfunction "PB0_7") (pintype "passive"))
      (node (ref "POTA_OFFSET") (pin "8") (pinfunction "VDD_8") (pintype "power_in"))
      (node (ref "POTB_GAIN") (pin "8") (pinfunction "VDD_8") (pintype "power_in"))
      (node (ref "POTB_OFFSET") (pin "7") (pinfunction "PB0_7") (pintype "passive"))
      (node (ref "POTB_OFFSET") (pin "8") (pinfunction "VDD_8") (pintype "power_in"))
      (node (ref "R1") (pin "2") (pinfunction "2_2") (pintype "passive"))
      (node (ref "R12") (pin "2") (pinfunction "2_2") (pintype "passive"))
      (node (ref "UT1") (pin "8") (pinfunction "VDD_8") (pintype "power_in"))
      (node (ref "UV1") (pin "4") (pinfunction "VDD_4") (pintype "power_in"))
      (node (ref "dsPIC33FJ16GS502") (pin "13") (pinfunction "VDD_13") (pintype "power_in"))
      (node (ref "dsPIC33FJ16GS502") (pin "28") (pinfunction "AVDD_28") (pintype "power_in"))
    )
    (net (code "65") (name "VCC-H") (class "Default")
      (node (ref "2") (pin "7") (pinfunction "VE_7") (pintype "passive"))
      (node (ref "2") (pin "8") (pinfunction "VCC_8") (pintype "passive"))
      (node (ref "B0505S-1W") (pin "2") (pinfunction "Vin_2") (pintype "passive"))
      (node (ref "C12") (pin "2") (pinfunction "2_2") (pintype "passive"))
      (node (ref "FT232RL") (pin "20") (pinfunction "VCC_20") (pintype "power_in"))
      (node (ref "FT232RL") (pin "4") (pinfunction "VCCIO_4") (pintype "power_in"))
      (node (ref "R16") (pin "1") (pinfunction "1_1") (pintype "passive"))
      (node (ref "R17") (pin "2") (pinfunction "2_2") (pintype "passive"))
      (node (ref "R5") (pin "2") (pinfunction "2_2") (pintype "passive"))
      (node (ref "RG1") (pin "2") (pinfunction "2_2") (pintype "passive"))
      (node (ref "RR1") (pin "2") (pinfunction "2_2") (pintype "passive"))
      (node (ref "USB-B") (pin "1") (pinfunction "VCC_1") (pintype "passive"))
    )
    (net (code "66") (name "unconnected-(FT232RL-CBUS2-Pad13)") (class "Default")
      (node (ref "FT232RL") (pin "13") (pinfunction "CBUS2_13") (pintype "bidirectional+no_connect"))
    )
    (net (code "67") (name "unconnected-(FT232RL-CBUS3-Pad14)") (class "Default")
      (node (ref "FT232RL") (pin "14") (pinfunction "CBUS3_14") (pintype "bidirectional+no_connect"))
    )
    (net (code "68") (name "unconnected-(FT232RL-CBUS4-Pad12)") (class "Default")
      (node (ref "FT232RL") (pin "12") (pinfunction "CBUS4_12") (pintype "bidirectional+no_connect"))
    )
    (net (code "69") (name "unconnected-(FT232RL-NC-Pad8)") (class "Default")
      (node (ref "FT232RL") (pin "8") (pinfunction "NC_8") (pintype "passive+no_connect"))
    )
    (net (code "70") (name "unconnected-(FT232RL-NC-Pad24)") (class "Default")
      (node (ref "FT232RL") (pin "24") (pinfunction "NC_24") (pintype "passive+no_connect"))
    )
    (net (code "71") (name "unconnected-(FT232RL-OSCI-Pad27)") (class "Default")
      (node (ref "FT232RL") (pin "27") (pinfunction "OSCI_27") (pintype "input+no_connect"))
    )
    (net (code "72") (name "unconnected-(FT232RL-OSCO-Pad28)") (class "Default")
      (node (ref "FT232RL") (pin "28") (pinfunction "OSCO_28") (pintype "output+no_connect"))
    )
    (net (code "73") (name "unconnected-(FT232RL-~{CTS}-Pad11)") (class "Default")
      (node (ref "FT232RL") (pin "11") (pinfunction "~{CTS}_11") (pintype "input+no_connect"))
    )
    (net (code "74") (name "unconnected-(FT232RL-~{DCD}-Pad10)") (class "Default")
      (node (ref "FT232RL") (pin "10") (pinfunction "~{DCD}_10") (pintype "input+no_connect"))
    )
    (net (code "75") (name "unconnected-(FT232RL-~{DSR}-Pad9)") (class "Default")
      (node (ref "FT232RL") (pin "9") (pinfunction "~{DSR}_9") (pintype "input+no_connect"))
    )
    (net (code "76") (name "unconnected-(FT232RL-~{DTR}-Pad2)") (class "Default")
      (node (ref "FT232RL") (pin "2") (pinfunction "~{DTR}_2") (pintype "output+no_connect"))
    )
    (net (code "77") (name "unconnected-(FT232RL-~{RESET}-Pad19)") (class "Default")
      (node (ref "FT232RL") (pin "19") (pinfunction "~{RESET}_19") (pintype "input+no_connect"))
    )
    (net (code "78") (name "unconnected-(FT232RL-~{RI}-Pad6)") (class "Default")
      (node (ref "FT232RL") (pin "6") (pinfunction "~{RI}_6") (pintype "input+no_connect"))
    )
    (net (code "79") (name "unconnected-(FT232RL-~{RTS}-Pad3)") (class "Default")
      (node (ref "FT232RL") (pin "3") (pinfunction "~{RTS}_3") (pintype "output+no_connect"))
    )
    (net (code "80") (name "unconnected-(PIC-ICSP1-Pad6)") (class "Default")
      (node (ref "PIC-ICSP1") (pin "6") (pinfunction "6_6") (pintype "passive"))
    )
    (net (code "81") (name "unconnected-(U2-NC-Pad1)") (class "Default")
      (node (ref "U2") (pin "1") (pinfunction "NC_1") (pintype "passive"))
    )
    (net (code "82") (name "unconnected-(U2-OSC-Pad7)") (class "Default")
      (node (ref "U2") (pin "7") (pinfunction "OSC_7") (pintype "passive"))
    )
    (net (code "83") (name "unconnected-(USB-B-Pad5)") (class "Default")
      (node (ref "USB-B") (pin "5") (pinfunction "5_5") (pintype "passive"))
    )
    (net (code "84") (name "unconnected-(USB-B-Pad6)") (class "Default")
      (node (ref "USB-B") (pin "6") (pinfunction "6_6") (pintype "passive"))
    )
    (net (code "85") (name "unconnected-(dsPIC33FJ16GS502-AN2{slash}CMP1C{slash}CMP2A{slash}RA2-Pad4)") (class "Default")
      (node (ref "dsPIC33FJ16GS502") (pin "4") (pinfunction "AN2/CMP1C/CMP2A/RA2_4") (pintype "bidirectional+no_connect"))
    )
    (net (code "86") (name "unconnected-(dsPIC33FJ16GS502-AN3{slash}CMP1D{slash}CMP2B{slash}RP0{slash}CN0{slash}RB0-Pad5)") (class "Default")
      (node (ref "dsPIC33FJ16GS502") (pin "5") (pinfunction "AN3/CMP1D/CMP2B/RP0/CN0/RB0_5") (pintype "bidirectional+no_connect"))
    )
    (net (code "87") (name "unconnected-(dsPIC33FJ16GS502-AN4{slash}CMP2C{slash}CMP3A{slash}RP9{slash}CN9{slash}RB9-Pad6)") (class "Default")
      (node (ref "dsPIC33FJ16GS502") (pin "6") (pinfunction "AN4/CMP2C/CMP3A/RP9/CN9/RB9_6") (pintype "bidirectional+no_connect"))
    )
    (net (code "88") (name "unconnected-(dsPIC33FJ16GS502-AN5{slash}CMP2D{slash}CMP3B{slash}RP10{slash}CN10{slash}RB10-Pad7)") (class "Default")
      (node (ref "dsPIC33FJ16GS502") (pin "7") (pinfunction "AN5/CMP2D/CMP3B/RP10/CN10/RB10_7") (pintype "bidirectional+no_connect"))
    )
    (net (code "89") (name "unconnected-(dsPIC33FJ16GS502-PGEC2{slash}EXTREF{slash}RP4{slash}CN4{slash}RB4-Pad12)") (class "Default")
      (node (ref "dsPIC33FJ16GS502") (pin "12") (pinfunction "PGEC2/EXTREF/RP4/CN4/RB4_12") (pintype "bidirectional+no_connect"))
    )
    (net (code "90") (name "unconnected-(dsPIC33FJ16GS502-PGED2{slash}DACOUT{slash}INT0{slash}RP3{slash}CN3{slash}RB3-Pad11)") (class "Default")
      (node (ref "dsPIC33FJ16GS502") (pin "11") (pinfunction "PGED2/DACOUT/INT0/RP3/CN3/RB3_11") (pintype "bidirectional+no_connect"))
    )
    (net (code "91") (name "unconnected-(dsPIC33FJ16GS502-TDO{slash}RP5{slash}CN6{slash}RB5-Pad16)") (class "Default")
      (node (ref "dsPIC33FJ16GS502") (pin "16") (pinfunction "TDO/RP5/CN6/RB5_16") (pintype "bidirectional+no_connect"))
    )
  )
)
